# Electronic_Dice_Schematic.net
KiCad netlist of a schematic drawn in EasyEDA
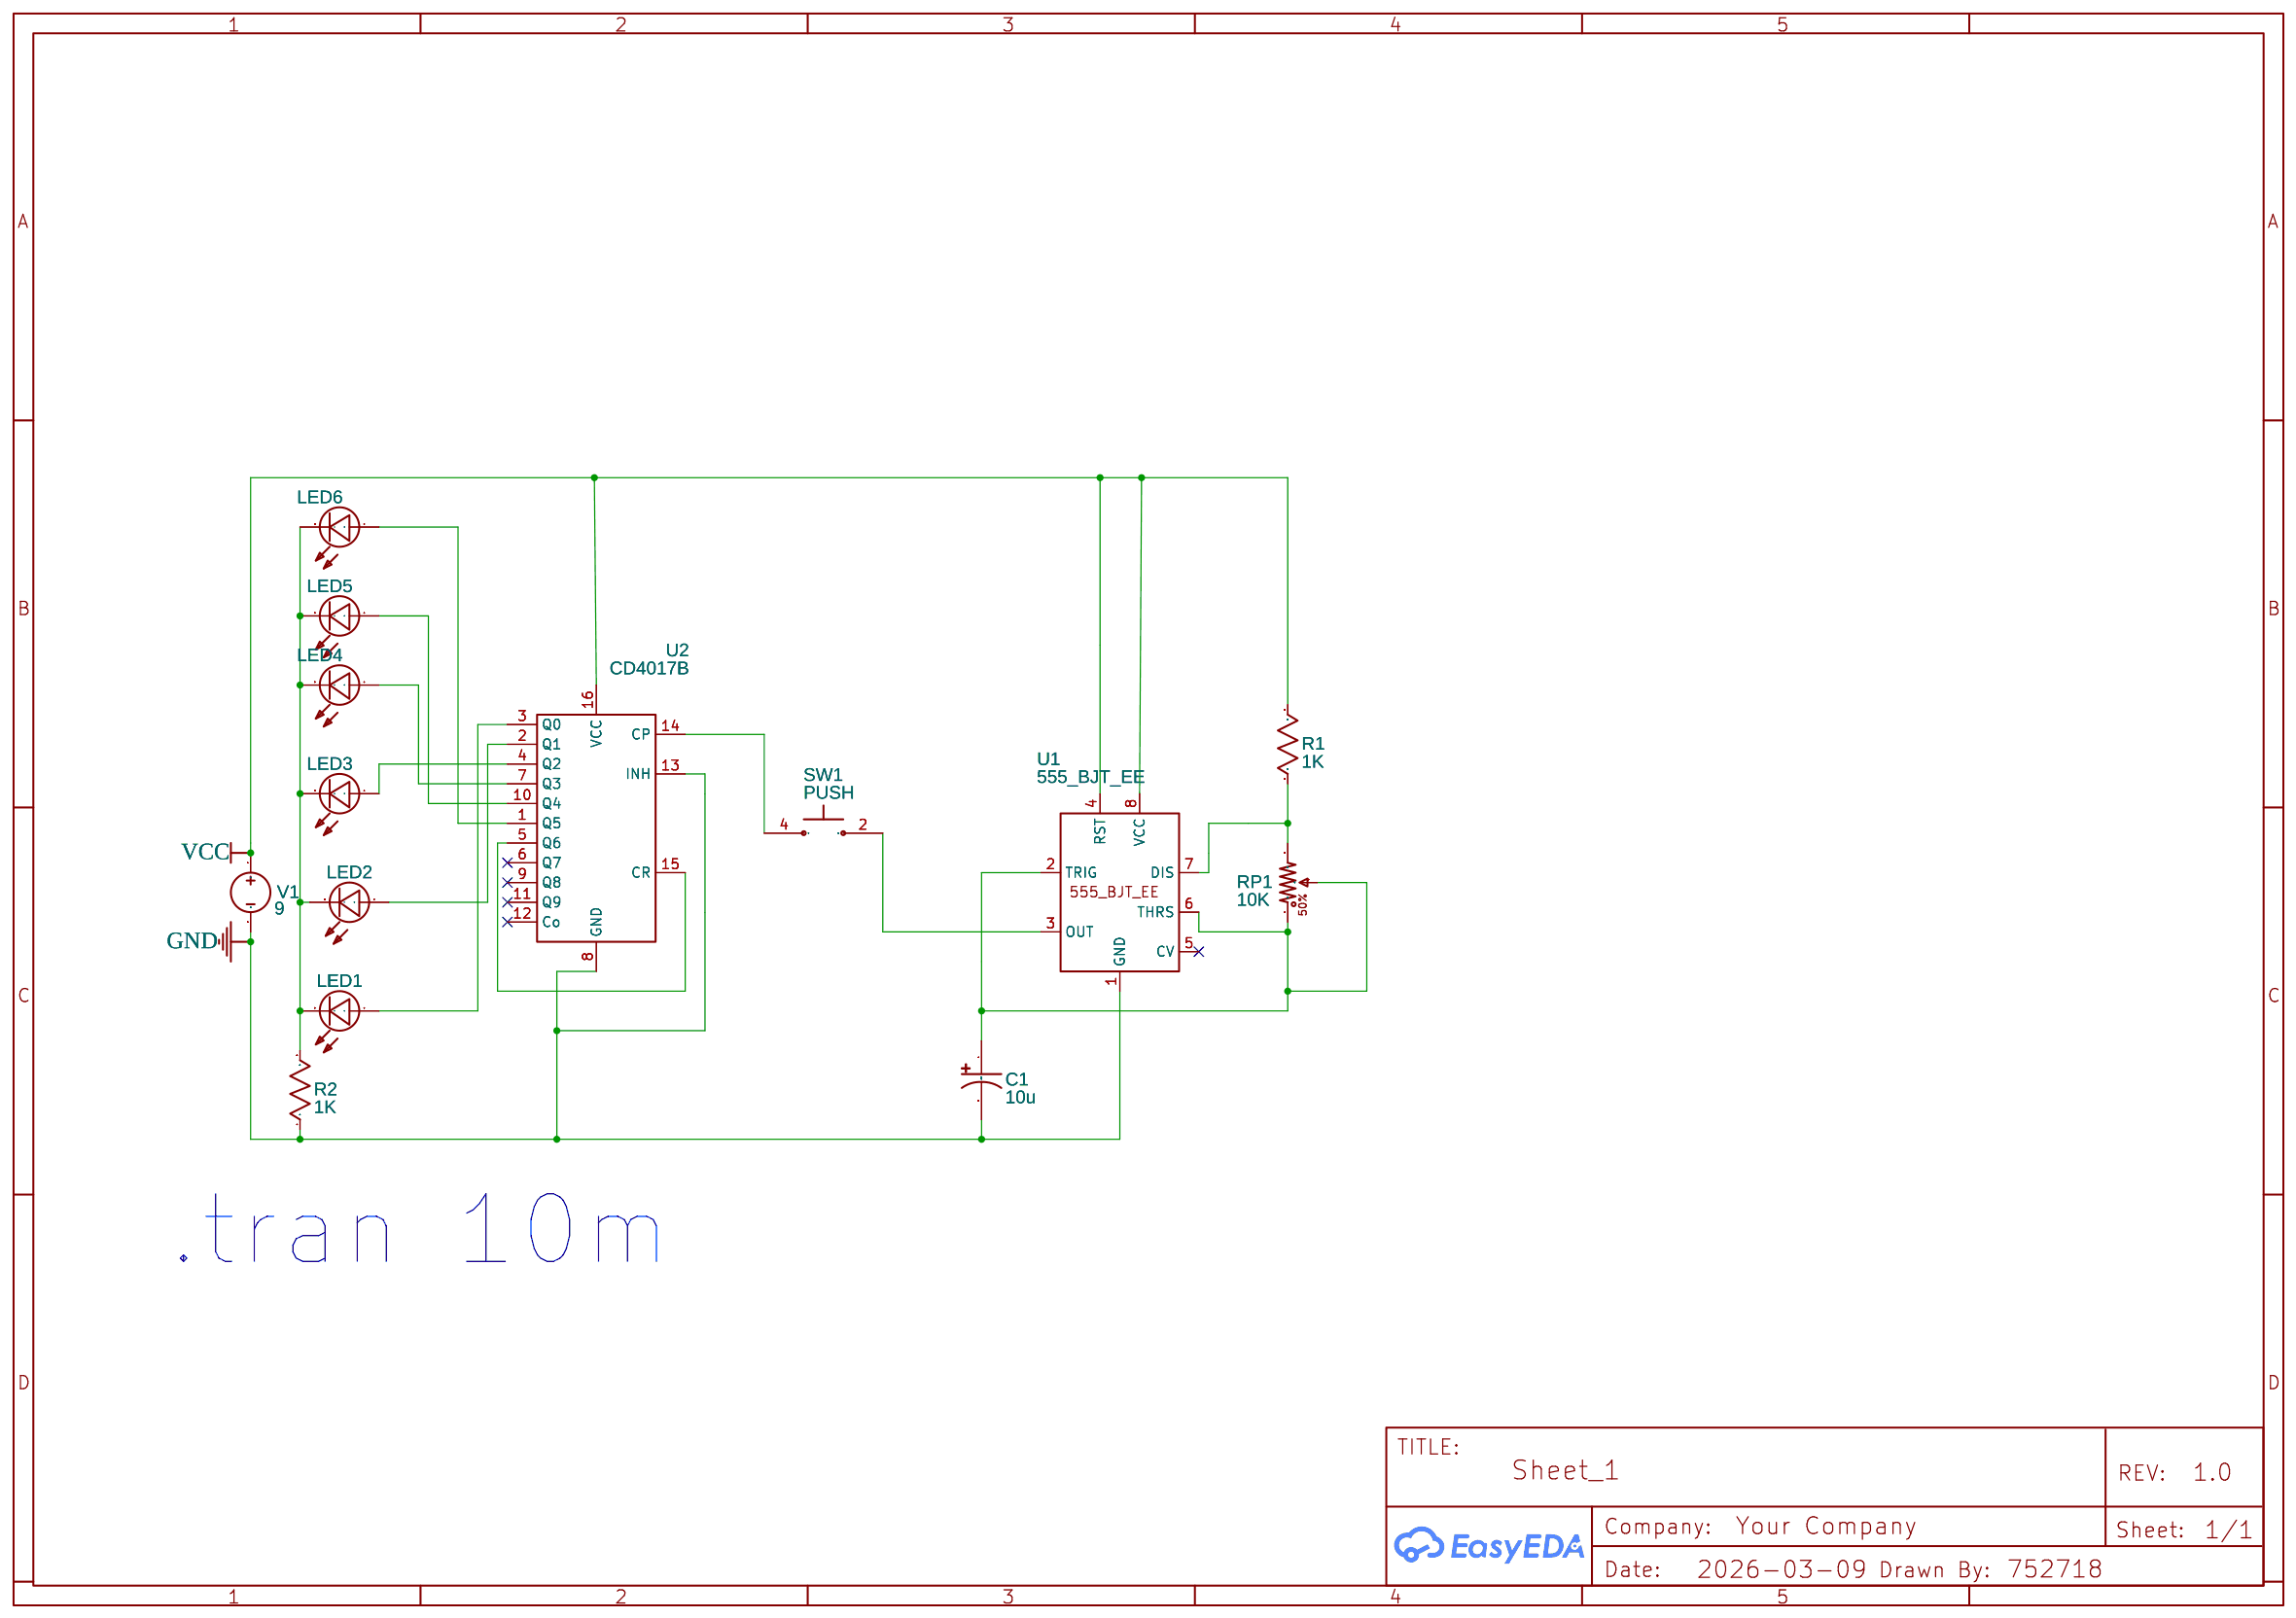
[diagram p0: schematic sheet]

(export (version "E")
  (design (tool "Eeschema 10.0.6"))
  (components
    (comp (ref "C1") (value "10u") (libsource (lib "") (part "Capacitor_Electrolytic_US")))
    (comp (ref "LED1") (value "LED") (libsource (lib "") (part "LED")))
    (comp (ref "LED2") (value "LED") (libsource (lib "") (part "LED")))
    (comp (ref "LED3") (value "LED") (libsource (lib "") (part "LED")))
    (comp (ref "LED4") (value "LED") (libsource (lib "") (part "LED")))
    (comp (ref "LED5") (value "LED") (libsource (lib "") (part "LED")))
    (comp (ref "LED6") (value "LED") (libsource (lib "") (part "LED")))
    (comp (ref "R1") (value "1K") (libsource (lib "") (part "Resistor_US")))
    (comp (ref "R2") (value "1K") (libsource (lib "") (part "Resistor_US")))
    (comp (ref "RP1") (value "10K") (libsource (lib "") (part "POTENTIOMETER")))
    (comp (ref "SW1") (value "PUSH") (libsource (lib "") (part "PUSHBUTTON COPY")))
    (comp (ref "U1") (value "555_BJT_EE") (libsource (lib "") (part "555_BJT_EE")))
    (comp (ref "U2") (value "CD4017B") (libsource (lib "") (part "4KHEF")))
    (comp (ref "V1") (value "9") (libsource (lib "") (part "VDC")))
  )
  (nets
    (net (code "1") (name "GND") (class "Default")
      (node (ref "C1") (pin "2") (pinfunction "2_2") (pintype "unspecified"))
      (node (ref "R2") (pin "1") (pinfunction "1_1") (pintype "unspecified"))
      (node (ref "U1") (pin "1") (pinfunction "GND_1") (pintype "unspecified"))
      (node (ref "U2") (pin "13") (pinfunction "INH_13") (pintype "unspecified"))
      (node (ref "U2") (pin "8") (pinfunction "GND_8") (pintype "unspecified"))
      (node (ref "V1") (pin "2") (pinfunction "2_2") (pintype "unspecified"))
    )
    (net (code "2") (name "Net-(LED1-+)") (class "Default")
      (node (ref "LED1") (pin "1") (pinfunction "+_1") (pintype "unspecified"))
      (node (ref "U2") (pin "3") (pinfunction "Q0_3") (pintype "unspecified"))
    )
    (net (code "3") (name "Net-(LED1--)") (class "Default")
      (node (ref "LED1") (pin "2") (pinfunction "-_2") (pintype "unspecified"))
      (node (ref "LED2") (pin "2") (pinfunction "-_2") (pintype "unspecified"))
      (node (ref "LED3") (pin "2") (pinfunction "-_2") (pintype "unspecified"))
      (node (ref "LED4") (pin "2") (pinfunction "-_2") (pintype "unspecified"))
      (node (ref "LED5") (pin "2") (pinfunction "-_2") (pintype "unspecified"))
      (node (ref "LED6") (pin "2") (pinfunction "-_2") (pintype "unspecified"))
      (node (ref "R2") (pin "2") (pinfunction "2_2") (pintype "unspecified"))
    )
    (net (code "4") (name "Net-(LED2-+)") (class "Default")
      (node (ref "LED2") (pin "1") (pinfunction "+_1") (pintype "unspecified"))
      (node (ref "U2") (pin "2") (pinfunction "Q1_2") (pintype "unspecified"))
    )
    (net (code "5") (name "Net-(LED3-+)") (class "Default")
      (node (ref "LED3") (pin "1") (pinfunction "+_1") (pintype "unspecified"))
      (node (ref "U2") (pin "4") (pinfunction "Q2_4") (pintype "unspecified"))
    )
    (net (code "6") (name "Net-(LED4-+)") (class "Default")
      (node (ref "LED4") (pin "1") (pinfunction "+_1") (pintype "unspecified"))
      (node (ref "U2") (pin "7") (pinfunction "Q3_7") (pintype "unspecified"))
    )
    (net (code "7") (name "Net-(LED5-+)") (class "Default")
      (node (ref "LED5") (pin "1") (pinfunction "+_1") (pintype "unspecified"))
      (node (ref "U2") (pin "10") (pinfunction "Q4_10") (pintype "unspecified"))
    )
    (net (code "8") (name "Net-(LED6-+)") (class "Default")
      (node (ref "LED6") (pin "1") (pinfunction "+_1") (pintype "unspecified"))
      (node (ref "U2") (pin "1") (pinfunction "Q5_1") (pintype "unspecified"))
    )
    (net (code "9") (name "Net-(SW1-1)") (class "Default")
      (node (ref "SW1") (pin "4") (pinfunction "1_4") (pintype "unspecified"))
      (node (ref "U2") (pin "14") (pinfunction "CP_14") (pintype "unspecified"))
    )
    (net (code "10") (name "Net-(U1-DIS)") (class "Default")
      (node (ref "R1") (pin "1") (pinfunction "1_1") (pintype "unspecified"))
      (node (ref "RP1") (pin "3") (pinfunction "3_3") (pintype "unspecified"))
      (node (ref "U1") (pin "7") (pinfunction "DIS_7") (pintype "unspecified"))
    )
    (net (code "11") (name "Net-(U1-OUT)") (class "Default")
      (node (ref "SW1") (pin "2") (pinfunction "2_2") (pintype "unspecified"))
      (node (ref "U1") (pin "3") (pinfunction "OUT_3") (pintype "unspecified"))
    )
    (net (code "12") (name "Net-(U1-THRS)") (class "Default")
      (node (ref "C1") (pin "1") (pinfunction "1_1") (pintype "unspecified"))
      (node (ref "RP1") (pin "1") (pinfunction "1_1") (pintype "unspecified"))
      (node (ref "RP1") (pin "2") (pinfunction "2_2") (pintype "unspecified"))
      (node (ref "U1") (pin "2") (pinfunction "TRIG_2") (pintype "unspecified"))
      (node (ref "U1") (pin "6") (pinfunction "THRS_6") (pintype "unspecified"))
    )
    (net (code "13") (name "Net-(U2-CR)") (class "Default")
      (node (ref "U2") (pin "15") (pinfunction "CR_15") (pintype "unspecified"))
      (node (ref "U2") (pin "5") (pinfunction "Q6_5") (pintype "unspecified"))
    )
    (net (code "14") (name "VCC") (class "Default")
      (node (ref "R1") (pin "2") (pinfunction "2_2") (pintype "unspecified"))
      (node (ref "U1") (pin "4") (pinfunction "RST_4") (pintype "unspecified"))
      (node (ref "U1") (pin "8") (pinfunction "VCC_8") (pintype "unspecified"))
      (node (ref "U2") (pin "16") (pinfunction "VCC_16") (pintype "unspecified"))
      (node (ref "V1") (pin "1") (pinfunction "1_1") (pintype "unspecified"))
    )
    (net (code "15") (name "unconnected-(U1-CV-Pad5)") (class "Default")
      (node (ref "U1") (pin "5") (pinfunction "CV_5") (pintype "unspecified+no_connect"))
    )
    (net (code "16") (name "unconnected-(U2-Co-Pad12)") (class "Default")
      (node (ref "U2") (pin "12") (pinfunction "Co_12") (pintype "unspecified+no_connect"))
    )
    (net (code "17") (name "unconnected-(U2-Q7-Pad6)") (class "Default")
      (node (ref "U2") (pin "6") (pinfunction "Q7_6") (pintype "unspecified+no_connect"))
    )
    (net (code "18") (name "unconnected-(U2-Q8-Pad9)") (class "Default")
      (node (ref "U2") (pin "9") (pinfunction "Q8_9") (pintype "unspecified+no_connect"))
    )
    (net (code "19") (name "unconnected-(U2-Q9-Pad11)") (class "Default")
      (node (ref "U2") (pin "11") (pinfunction "Q9_11") (pintype "unspecified+no_connect"))
    )
  )
)
